# LEDS_-_Status.net
KiCad netlist of a schematic drawn in Altium Designer
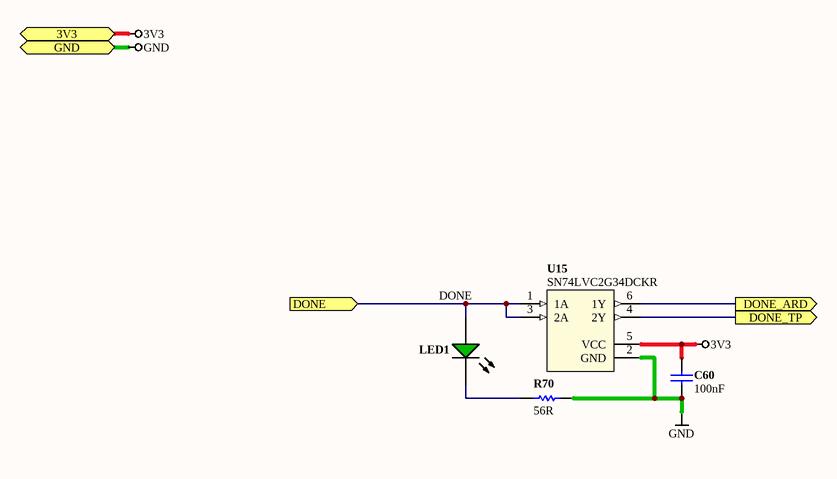
[diagram p0: LEDS - Status.SchDoc]

(export (version "E")
  (design (tool "Eeschema 10.0.6"))
  (components
    (comp (ref "C60")
      (value "100nF")
      (footprint "CAPC0402(1005)60_L")
      (description "CAP 100nF 10V ±5% 0402 (1005 Metric) Thickness 0.6mm SMD")
      (fields (field (name "TOLERANCE") "±5%") (field (name "Comment") "CAP 100nF 10V 0402(1005)"))
      (libsource (lib "Altium Content Vault") (part "CMP-1034-02064-1"))
    )
    (comp (ref "LED1")
      (value "LED_GREEN_APT1608SGC")
      (footprint "LED0603")
      (description "SMD 0603 LED, GREEN")
      (fields (field (name "PARTNUMBER") "APT1608SGC"))
      (libsource (lib "LED-GREEN-APT1608SGC") (part "LED_GREEN_APT1608SGC"))
    )
    (comp (ref "R70")
      (value "56R")
      (footprint "RESC0402(1005)_L")
      (description "56R 0.063W 1% 0402 (1005 Metric)  SMD")
      (fields (field (name "POWER") "0.063 W") (field (name "TOLERANCE") "1 %"))
      (libsource (lib "Altium Content Vault") (part "CMP-1011-00369-1"))
    )
    (comp (ref "U15")
      (value "SN74LVC2G34DCKR")
      (footprint "TI-DCK6_L")
      (description "IC BUFFER DUAL NON-INV SC706")
      (fields (field (name "MANUFACTURER") "Texas Instruments"))
      (libsource (lib "Component_Database") (part "SN74LVC2G34"))
    )
  )
  (nets
    (net (code "1") (name "/DONE") (class "Default")
      (node (ref "LED1") (pin "1") (pinfunction "A_1") (pintype "passive"))
      (node (ref "U15") (pin "1") (pinfunction "1A_1") (pintype "input"))
      (node (ref "U15") (pin "3") (pinfunction "2A_3") (pintype "input"))
    )
    (net (code "2") (name "/DONE_ARD") (class "Default")
      (node (ref "U15") (pin "6") (pinfunction "1Y_6") (pintype "output"))
    )
    (net (code "3") (name "/DONE_TP") (class "Default")
      (node (ref "U15") (pin "4") (pinfunction "2Y_4") (pintype "output"))
    )
    (net (code "4") (name "3V3") (class "Default")
      (node (ref "C60") (pin "2") (pinfunction "2_2") (pintype "passive"))
      (node (ref "U15") (pin "5") (pinfunction "VCC_5") (pintype "power_in"))
    )
    (net (code "5") (name "GND") (class "Default")
      (node (ref "C60") (pin "1") (pinfunction "1_1") (pintype "passive"))
      (node (ref "R70") (pin "2") (pinfunction "2_2") (pintype "passive"))
      (node (ref "U15") (pin "2") (pinfunction "GND_2") (pintype "power_in"))
    )
    (net (code "6") (name "Net-(LED1-K)") (class "Default")
      (node (ref "LED1") (pin "2") (pinfunction "K_2") (pintype "passive"))
      (node (ref "R70") (pin "1") (pinfunction "1_1") (pintype "passive"))
    )
  )
)
